# Power_adacus_sch.net
KiCad netlist of a schematic drawn in Altium Designer
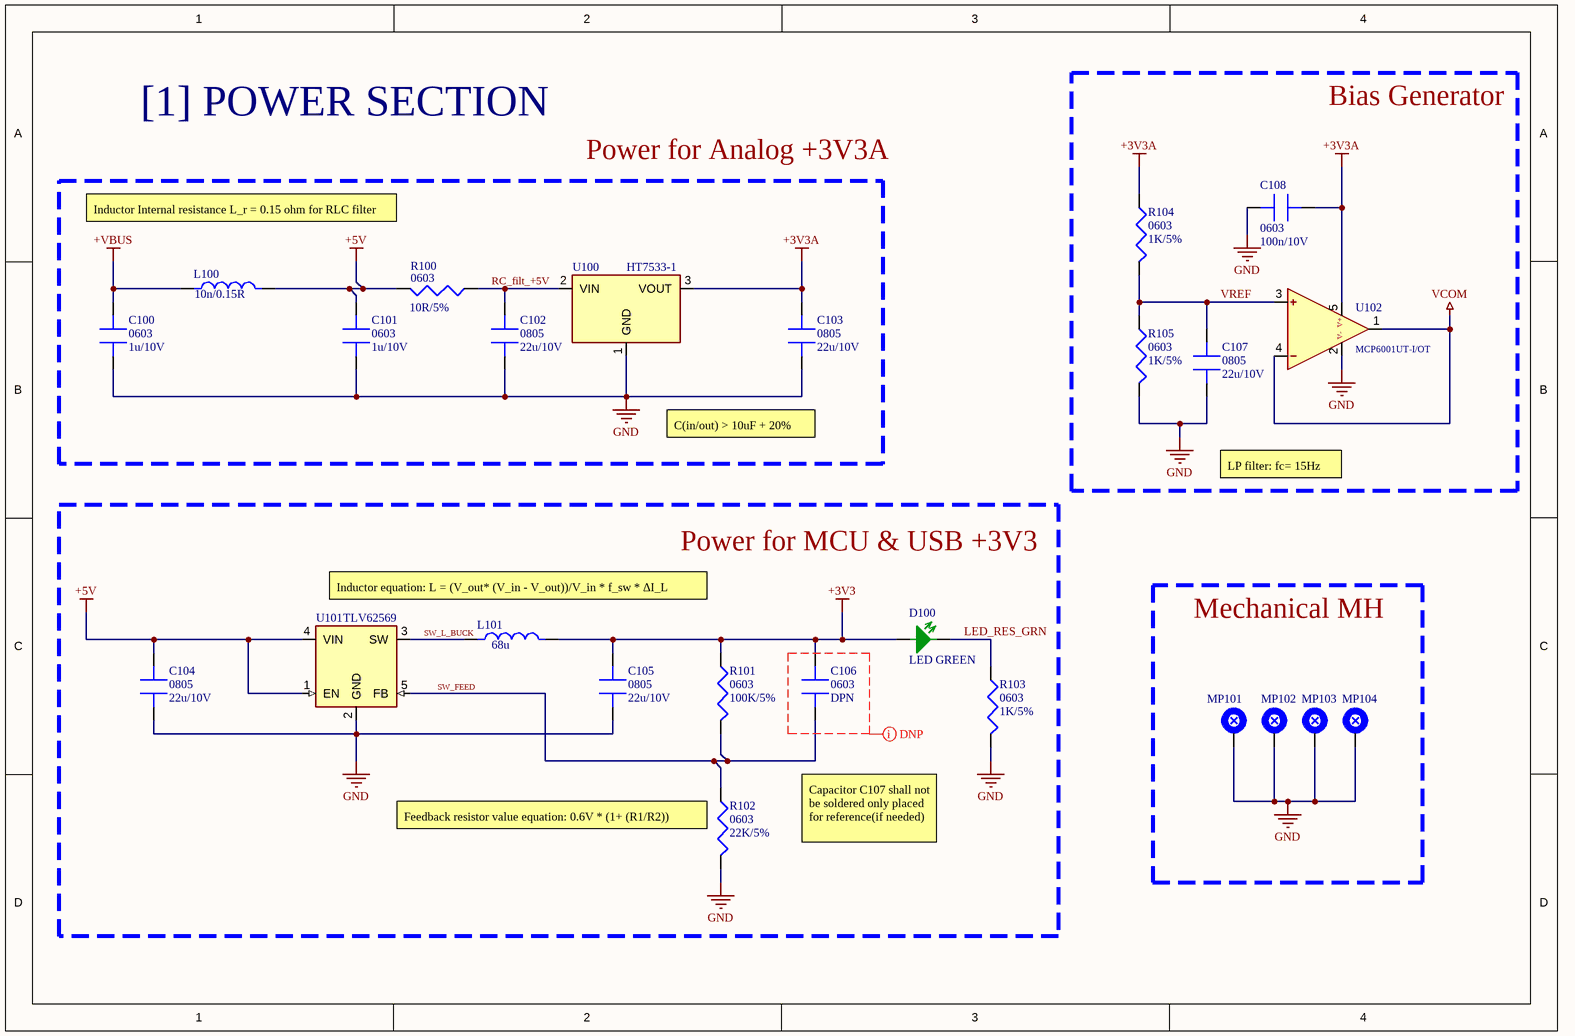
[diagram p0: Power_adacus_sch.SchDoc]

(export (version "E")
  (design (tool "Eeschema 10.0.6"))
  (components
    (comp (ref "C100")
      (value "1u/10V")
      (footprint "[0603] CAPC1608X10M [A-LD]")
      (description "Standard Capacitor")
      (fields (field (name "PACKAGE") "0603") (field (name "Comment") "Capacitor"))
      (libsource (lib "adacus_schlib") (part "Capacitor"))
    )
    (comp (ref "C101")
      (value "1u/10V")
      (footprint "[0603] CAPC1608X10M [A-LD]")
      (description "Standard Capacitor")
      (fields (field (name "PACKAGE") "0603") (field (name "Comment") "Capacitor"))
      (libsource (lib "adacus_schlib") (part "Capacitor"))
    )
    (comp (ref "C102")
      (value "22u/10V")
      (footprint "[0805] CAPC2012X09M [A - LD]")
      (description "Standard Capacitor")
      (fields (field (name "PACKAGE") "0805") (field (name "Comment") "Capacitor"))
      (libsource (lib "adacus_schlib") (part "Capacitor"))
    )
    (comp (ref "C103")
      (value "22u/10V")
      (footprint "[0805] CAPC2012X09M [A - LD]")
      (description "Standard Capacitor")
      (fields (field (name "PACKAGE") "0805") (field (name "Comment") "Capacitor"))
      (libsource (lib "adacus_schlib") (part "Capacitor"))
    )
    (comp (ref "C104")
      (value "22u/10V")
      (footprint "[0805] CAPC2012X09M [A - LD]")
      (description "Standard Capacitor")
      (fields (field (name "PACKAGE") "0805") (field (name "Comment") "Capacitor"))
      (libsource (lib "adacus_schlib") (part "Capacitor"))
    )
    (comp (ref "C105")
      (value "22u/10V")
      (footprint "[0805] CAPC2012X09M [A - LD]")
      (description "Standard Capacitor")
      (fields (field (name "PACKAGE") "0805") (field (name "Comment") "Capacitor"))
      (libsource (lib "adacus_schlib") (part "Capacitor"))
    )
    (comp (ref "C106")
      (value "DPN")
      (footprint "[0603] CAPC1608X10M [A-LD]")
      (description "Standard Capacitor")
      (fields (field (name "PACKAGE") "0603") (field (name "Comment") "Capacitor"))
      (libsource (lib "adacus_schlib") (part "Capacitor"))
    )
    (comp (ref "C107")
      (value "22u/10V")
      (footprint "[0805] CAPC2012X09M [A - LD]")
      (description "Standard Capacitor")
      (fields (field (name "PACKAGE") "0805") (field (name "Comment") "Capacitor"))
      (libsource (lib "adacus_schlib") (part "Capacitor"))
    )
    (comp (ref "C108")
      (value "100n/10V")
      (footprint "[0603] CAPC1608X10M [A-LD]")
      (description "Standard Capacitor")
      (fields (field (name "PACKAGE") "0603") (field (name "Comment") "Capacitor"))
      (libsource (lib "adacus_schlib") (part "Capacitor"))
    )
    (comp (ref "D100")
      (value "LED GREEN")
      (footprint "LEDC2012X120N")
      (description "Standard LED. Green color")
      (libsource (lib "adacus_schlib") (part "LED GREEN"))
    )
    (comp (ref "L100")
      (value "10n/0.15R")
      (footprint "PM0603-10NJ")
      (description "Standard Inductor")
      (fields (field (name "Comment") "Inductor"))
      (libsource (lib "adacus_schlib") (part "Inductor"))
    )
    (comp (ref "L101")
      (value "68u")
      (footprint "[L] SPM10054T-680M-HZR")
      (description "Standard Inductor")
      (fields (field (name "Comment") "Inductor"))
      (libsource (lib "adacus_schlib") (part "Inductor"))
    )
    (comp (ref "MP101")
      (value "Mounting hole")
      (footprint "Mounting_hole_M3")
      (libsource (lib "SR_Library") (part "Mounting hole"))
    )
    (comp (ref "MP102")
      (value "Mounting hole")
      (footprint "Mounting_hole_M3")
      (libsource (lib "SR_Library") (part "Mounting hole"))
    )
    (comp (ref "MP103")
      (value "Mounting hole")
      (footprint "Mounting_hole_M3")
      (libsource (lib "SR_Library") (part "Mounting hole"))
    )
    (comp (ref "MP104")
      (value "Mounting hole")
      (footprint "Mounting_hole_M3")
      (libsource (lib "SR_Library") (part "Mounting hole"))
    )
    (comp (ref "R100")
      (value "10R/5%")
      (footprint "[0603] RESC1608X06M [A-LD]")
      (description "Standard Resistor")
      (fields (field (name "PACKAGE") "0603") (field (name "Comment") "Resistor"))
      (libsource (lib "adacus_schlib") (part "Resistor"))
    )
    (comp (ref "R101")
      (value "100K/5%")
      (footprint "[0603] RESC1608X06M [A-LD]")
      (description "Standard Resistor")
      (fields (field (name "PACKAGE") "0603") (field (name "Comment") "Resistor"))
      (libsource (lib "adacus_schlib") (part "Resistor"))
    )
    (comp (ref "R102")
      (value "22K/5%")
      (footprint "[0603] RESC1608X06M [A-LD]")
      (description "Standard Resistor")
      (fields (field (name "PACKAGE") "0603") (field (name "Comment") "Resistor"))
      (libsource (lib "adacus_schlib") (part "Resistor"))
    )
    (comp (ref "R103")
      (value "1K/5%")
      (footprint "[0603] RESC1608X06M [A-LD]")
      (description "Standard Resistor")
      (fields (field (name "PACKAGE") "0603") (field (name "Comment") "Resistor"))
      (libsource (lib "adacus_schlib") (part "Resistor"))
    )
    (comp (ref "R104")
      (value "1K/5%")
      (footprint "[0603] RESC1608X06M [A-LD]")
      (description "Standard Resistor")
      (fields (field (name "PACKAGE") "0603") (field (name "Comment") "Resistor"))
      (libsource (lib "adacus_schlib") (part "Resistor"))
    )
    (comp (ref "R105")
      (value "1K/5%")
      (footprint "[0603] RESC1608X06M [A-LD]")
      (description "Standard Resistor")
      (fields (field (name "PACKAGE") "0603") (field (name "Comment") "Resistor"))
      (libsource (lib "adacus_schlib") (part "Resistor"))
    )
    (comp (ref "U100")
      (value "HT7533-1")
      (footprint "SOT89-150P354X160-3M")
      (description "100mA TinyPower LDO")
      (libsource (lib "adacus_schlib") (part "HT7533-1"))
    )
    (comp (ref "U101")
      (value "TLV62569")
      (footprint "SOT95P280X145-5M")
      (description "2-A High Efficiency Synchronous Buck Converter in SOT Package")
      (libsource (lib "adacus_schlib") (part "TLV62569"))
    )
    (comp (ref "U102")
      (value "MCP6001UT-I/OT")
      (footprint "SOT95P270X145-5M")
      (description "Operational Amplifiers - Op Amps Single 1.8V 1MHz")
      (libsource (lib "adacus_schlib") (part "MCP6001UT-I/OT"))
    )
  )
  (nets
    (net (code "1") (name "+3V3") (class "Default")
      (node (ref "C105") (pin "2") (pinfunction "2_2") (pintype "passive"))
      (node (ref "C106") (pin "2") (pinfunction "2_2") (pintype "passive"))
      (node (ref "D100") (pin "1") (pinfunction "1_1") (pintype "passive"))
      (node (ref "L101") (pin "1") (pinfunction "1_1") (pintype "passive"))
      (node (ref "R101") (pin "2") (pinfunction "2_2") (pintype "passive"))
    )
    (net (code "2") (name "+3V3A") (class "Default")
      (node (ref "C103") (pin "2") (pinfunction "2_2") (pintype "passive"))
      (node (ref "C108") (pin "1") (pinfunction "1_1") (pintype "passive"))
      (node (ref "R104") (pin "2") (pinfunction "2_2") (pintype "passive"))
      (node (ref "U100") (pin "3") (pinfunction "VOUT_3") (pintype "power_in"))
      (node (ref "U102") (pin "5") (pinfunction "VDD_5") (pintype "passive"))
    )
    (net (code "3") (name "+5V") (class "Default")
      (node (ref "C101") (pin "2") (pinfunction "2_2") (pintype "passive"))
      (node (ref "C104") (pin "2") (pinfunction "2_2") (pintype "passive"))
      (node (ref "L100") (pin "1") (pinfunction "1_1") (pintype "passive"))
      (node (ref "R100") (pin "1") (pinfunction "1_1") (pintype "passive"))
      (node (ref "U101") (pin "1") (pinfunction "EN_1") (pintype "input"))
      (node (ref "U101") (pin "4") (pinfunction "VIN_4") (pintype "power_in"))
    )
    (net (code "4") (name "+VBUS") (class "Default")
      (node (ref "C100") (pin "2") (pinfunction "2_2") (pintype "passive"))
      (node (ref "L100") (pin "2") (pinfunction "2_2") (pintype "passive"))
    )
    (net (code "5") (name "/LED_RES_GRN") (class "Default")
      (node (ref "D100") (pin "2") (pinfunction "2_2") (pintype "passive"))
      (node (ref "R103") (pin "2") (pinfunction "2_2") (pintype "passive"))
    )
    (net (code "6") (name "/RC_filt_+5V") (class "Default")
      (node (ref "C102") (pin "2") (pinfunction "2_2") (pintype "passive"))
      (node (ref "R100") (pin "2") (pinfunction "2_2") (pintype "passive"))
      (node (ref "U100") (pin "2") (pinfunction "VIN_2") (pintype "power_in"))
    )
    (net (code "7") (name "/SW_FEED") (class "Default")
      (node (ref "C106") (pin "1") (pinfunction "1_1") (pintype "passive"))
      (node (ref "R101") (pin "1") (pinfunction "1_1") (pintype "passive"))
      (node (ref "R102") (pin "2") (pinfunction "2_2") (pintype "passive"))
      (node (ref "U101") (pin "5") (pinfunction "FB_5") (pintype "input"))
    )
    (net (code "8") (name "/SW_L_BUCK") (class "Default")
      (node (ref "L101") (pin "2") (pinfunction "2_2") (pintype "passive"))
      (node (ref "U101") (pin "3") (pinfunction "SW_3") (pintype "power_in"))
    )
    (net (code "9") (name "/VREF") (class "Default")
      (node (ref "C107") (pin "2") (pinfunction "2_2") (pintype "passive"))
      (node (ref "R104") (pin "1") (pinfunction "1_1") (pintype "passive"))
      (node (ref "R105") (pin "2") (pinfunction "2_2") (pintype "passive"))
      (node (ref "U102") (pin "3") (pinfunction "+_3") (pintype "passive"))
    )
    (net (code "10") (name "GND") (class "Default")
      (node (ref "C100") (pin "1") (pinfunction "1_1") (pintype "passive"))
      (node (ref "C101") (pin "1") (pinfunction "1_1") (pintype "passive"))
      (node (ref "C102") (pin "1") (pinfunction "1_1") (pintype "passive"))
      (node (ref "C103") (pin "1") (pinfunction "1_1") (pintype "passive"))
      (node (ref "C104") (pin "1") (pinfunction "1_1") (pintype "passive"))
      (node (ref "C105") (pin "1") (pinfunction "1_1") (pintype "passive"))
      (node (ref "C107") (pin "1") (pinfunction "1_1") (pintype "passive"))
      (node (ref "C108") (pin "2") (pinfunction "2_2") (pintype "passive"))
      (node (ref "MP101") (pin "1") (pinfunction "1_1") (pintype "passive"))
      (node (ref "MP102") (pin "1") (pinfunction "1_1") (pintype "passive"))
      (node (ref "MP103") (pin "1") (pinfunction "1_1") (pintype "passive"))
      (node (ref "MP104") (pin "1") (pinfunction "1_1") (pintype "passive"))
      (node (ref "R102") (pin "1") (pinfunction "1_1") (pintype "passive"))
      (node (ref "R103") (pin "1") (pinfunction "1_1") (pintype "passive"))
      (node (ref "R105") (pin "1") (pinfunction "1_1") (pintype "passive"))
      (node (ref "U100") (pin "1") (pinfunction "GND_1") (pintype "passive"))
      (node (ref "U101") (pin "2") (pinfunction "GND_2") (pintype "power_in"))
      (node (ref "U102") (pin "2") (pinfunction "VSS_2") (pintype "passive"))
    )
    (net (code "11") (name "VCOM") (class "Default")
      (node (ref "U102") (pin "1") (pinfunction "OUT_1") (pintype "passive"))
      (node (ref "U102") (pin "4") (pinfunction "-_4") (pintype "passive"))
    )
  )
)
